# eeZeeRGB.net
KiCad netlist of a schematic drawn in EAGLE
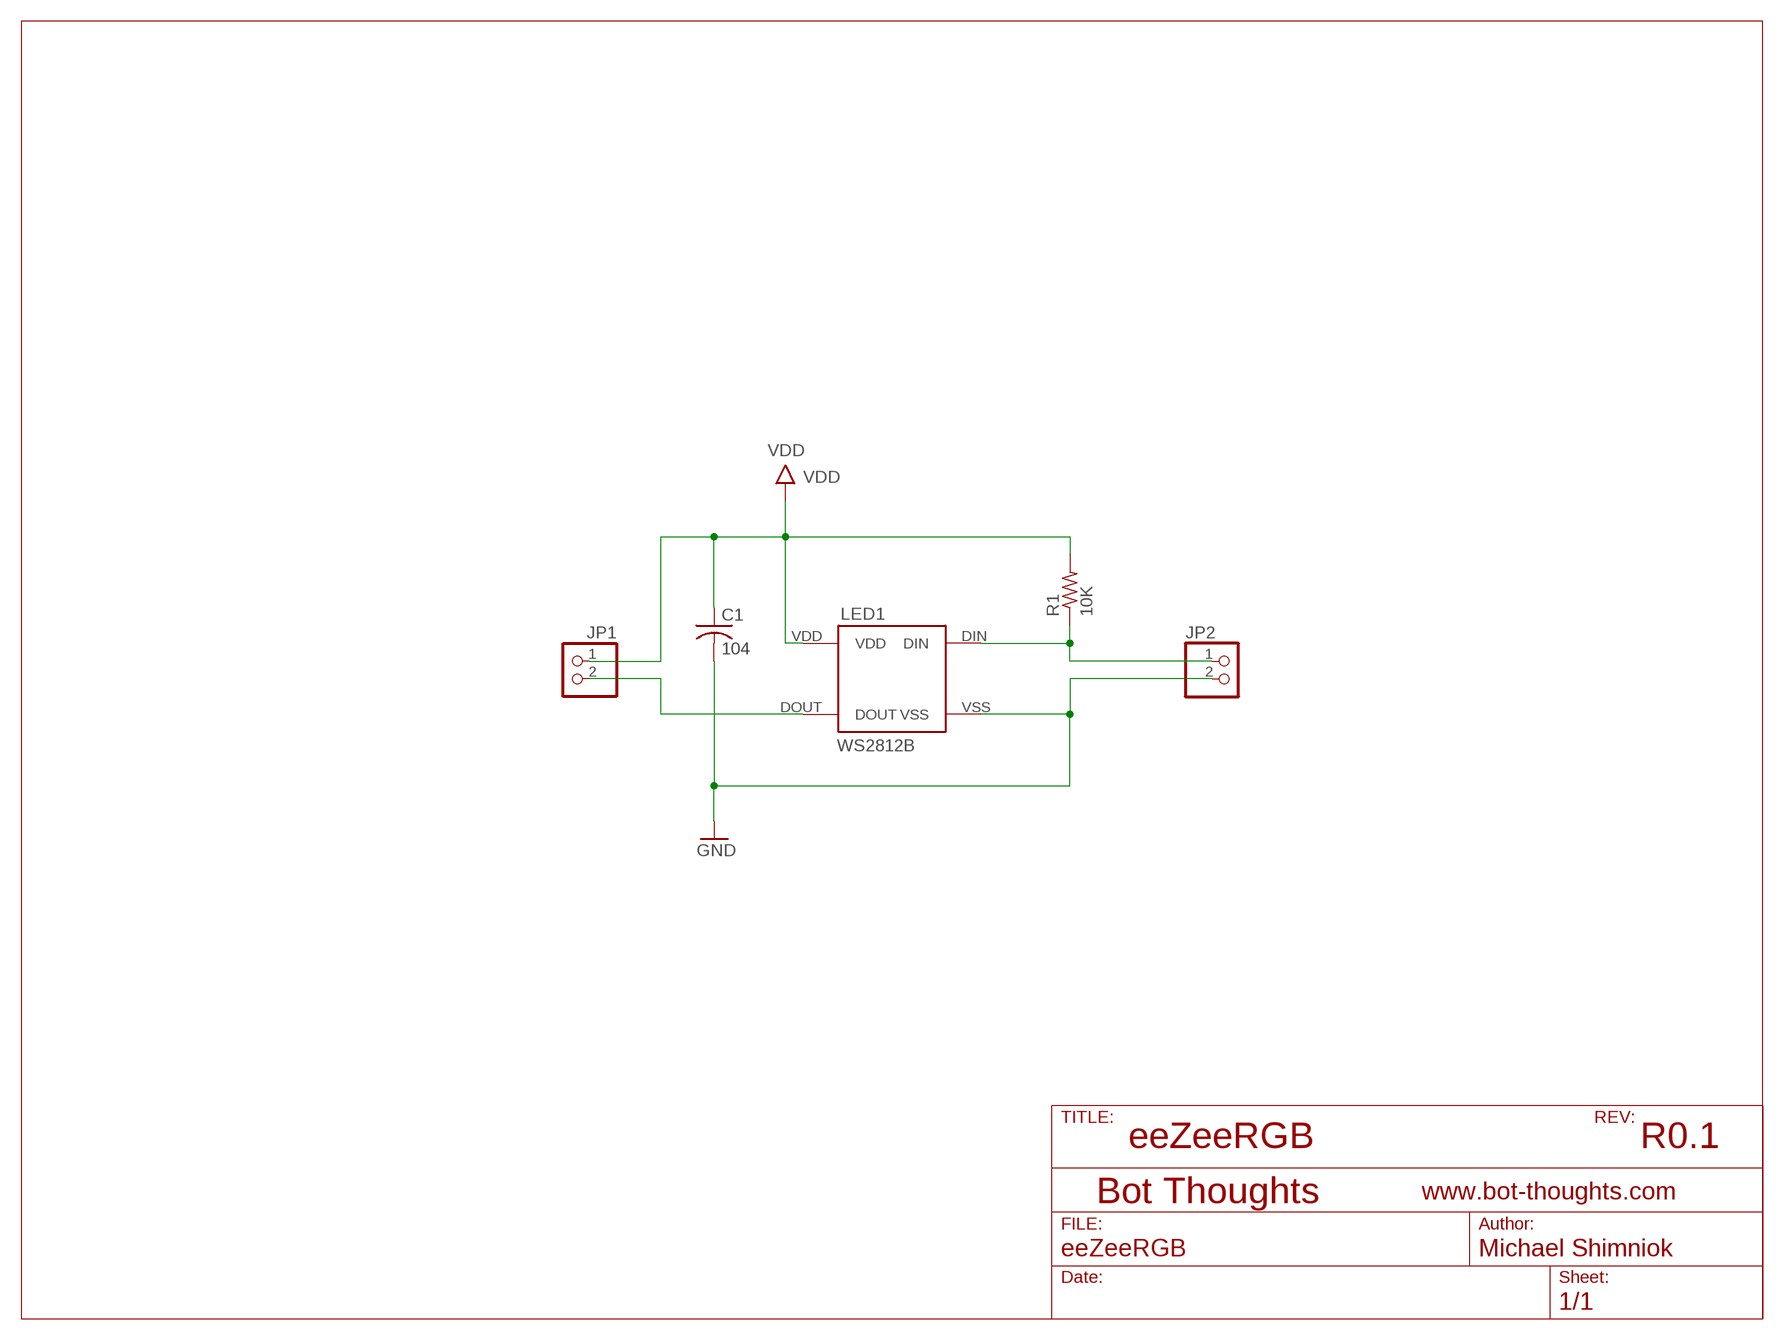
[diagram p0: schematic, sheet 1]

(export (version "E")
  (design (tool "Eeschema 10.0.6"))
  (components
    (comp (ref "C1")
      (value "104")
      (footprint "eagle-import:C0603")
      (libsource (lib "eagle-import") (part "C-USC0603"))
    )
    (comp (ref "JP1")
      (value "PINHD-1X02_2.54-S")
      (footprint "eagle-import:1X02-S")
      (libsource (lib "eagle-import") (part "PINHD-1X02_2.54-S"))
    )
    (comp (ref "JP2")
      (value "PINHD-1X02_2.54-S")
      (footprint "eagle-import:1X02-S")
      (libsource (lib "eagle-import") (part "PINHD-1X02_2.54-S"))
    )
    (comp (ref "LED1")
      (value "WS2812B")
      (footprint "eagle-import:WS2812B")
      (libsource (lib "eagle-import") (part "WS2812B"))
    )
    (comp (ref "R1")
      (value "10K")
      (footprint "eagle-import:R0603")
      (libsource (lib "eagle-import") (part "R-US_R0603"))
    )
  )
  (nets
    (net (code "1") (name "GND") (class "Default")
      (node (ref "C1") (pin "2") (pinfunction "2_2") (pintype "passive"))
      (node (ref "JP2") (pin "2") (pinfunction "2_2") (pintype "passive"))
      (node (ref "LED1") (pin "VSS") (pinfunction "VSS_VSS") (pintype "bidirectional"))
    )
    (net (code "2") (name "Net-(JP1-Pad2)") (class "Default")
      (node (ref "JP1") (pin "2") (pinfunction "2_2") (pintype "passive"))
      (node (ref "LED1") (pin "DOUT") (pinfunction "DOUT_DOUT") (pintype "bidirectional"))
    )
    (net (code "3") (name "Net-(JP2-Pad1)") (class "Default")
      (node (ref "JP2") (pin "1") (pinfunction "1_1") (pintype "passive"))
      (node (ref "LED1") (pin "DIN") (pinfunction "DIN_DIN") (pintype "bidirectional"))
      (node (ref "R1") (pin "1") (pinfunction "1_1") (pintype "passive"))
    )
    (net (code "4") (name "VDD") (class "Default")
      (node (ref "C1") (pin "1") (pinfunction "1_1") (pintype "passive"))
      (node (ref "JP1") (pin "1") (pinfunction "1_1") (pintype "passive"))
      (node (ref "LED1") (pin "VDD") (pinfunction "VDD_VDD") (pintype "bidirectional"))
      (node (ref "R1") (pin "2") (pinfunction "2_2") (pintype "passive"))
    )
  )
)
